# 03_SD_Card.net
KiCad netlist of a schematic drawn in Altium Designer
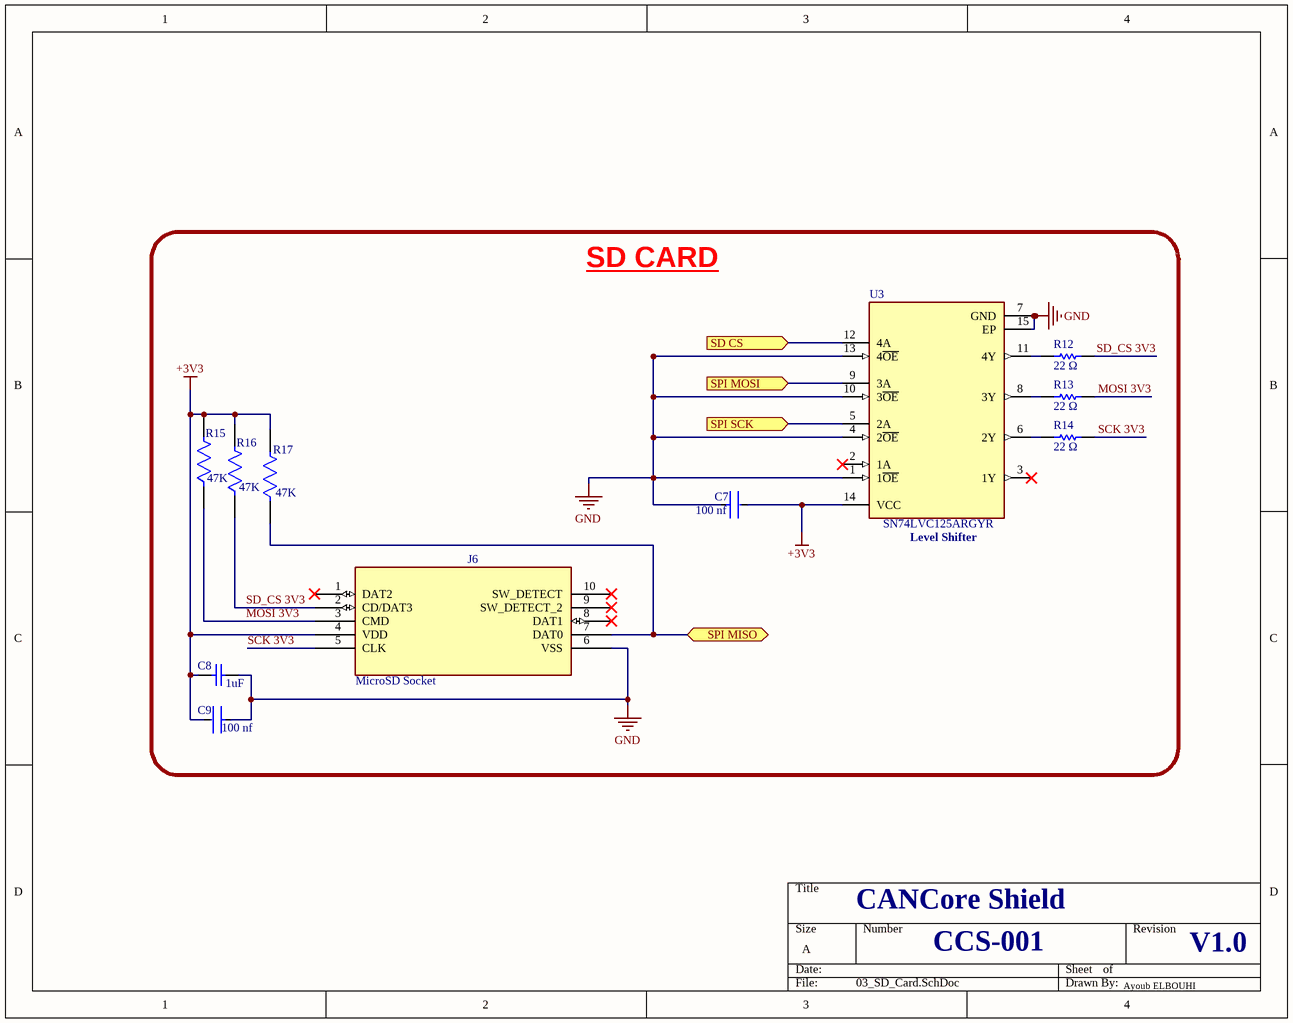
[diagram p0: 03_SD_Card.SchDoc]

(export (version "E")
  (design (tool "Eeschema 10.0.6"))
  (components
    (comp (ref "C7")
      (value "100 nf")
      (footprint "FP-0204-L_0_52_0_05-W_1_0-IPC_B")
      (description "None")
      (fields (field (name "TOLERANCE") "20%"))
      (libsource (lib "Altium Content Vault") (part "b4654b650e69147ec39a6b967a45e02"))
    )
    (comp (ref "C8")
      (value "1uF")
      (footprint "CAPC1608X90X35NL10T15")
      (fields (field (name "PART NUMBER") "GRM188R71A105KA61D") (field (name "MANUFACTURER") "Murata"))
      (libsource (lib "Altium Content Vault") (part "CAP"))
    )
    (comp (ref "C9")
      (value "100 nf")
      (footprint "FP-0204-L_0_52_0_05-W_1_0-IPC_B")
      (description "None")
      (fields (field (name "TOLERANCE") "20%"))
      (libsource (lib "Altium Content Vault") (part "b4654b650e69147ec39a6b967a45e02"))
    )
    (comp (ref "J6")
      (value "MicroSD Socket")
      (footprint "104031-0811_MOL")
      (fields (field (name "MF") "{'manufacturer': u'Molex'}") (field (name "MP") "1040310811"))
      (libsource (lib "1040310811") (part "1040310811"))
    )
    (comp (ref "R12")
      (value "22 Ω")
      (footprint "RESC1608X55X25ML10T15")
      (description "Chip Resistor, 22 Ohm, +/- 1%, 0.1 W, -55 to 155 degC, 0603 (1608 Metric), RoHS, Tape and Reel")
      (libsource (lib "Altium Content Vault") (part "RES-2"))
    )
    (comp (ref "R13")
      (value "22 Ω")
      (footprint "RESC1608X55X25ML10T15")
      (description "Chip Resistor, 22 Ohm, +/- 1%, 0.1 W, -55 to 155 degC, 0603 (1608 Metric), RoHS, Tape and Reel")
      (libsource (lib "Altium Content Vault") (part "RES-2"))
    )
    (comp (ref "R14")
      (value "22 Ω")
      (footprint "RESC1608X55X25ML10T15")
      (description "Chip Resistor, 22 Ohm, +/- 1%, 0.1 W, -55 to 155 degC, 0603 (1608 Metric), RoHS, Tape and Reel")
      (libsource (lib "Altium Content Vault") (part "RES-2"))
    )
    (comp (ref "R15")
      (value "47K")
      (footprint "FP-RC0603FR-0747KL-MFG")
      (description "RES SMD 47K OHM 1% 1/10W 0603")
      (fields (field (name "TOLERANCE") "1%"))
      (libsource (lib "Altium Content Vault") (part "1029c3af85768c4190bb7ad29bc67b5"))
    )
    (comp (ref "R16")
      (value "47K")
      (footprint "FP-RC0603FR-0747KL-MFG")
      (description "RES SMD 47K OHM 1% 1/10W 0603")
      (fields (field (name "TOLERANCE") "1%"))
      (libsource (lib "Altium Content Vault") (part "1029c3af85768c4190bb7ad29bc67b5"))
    )
    (comp (ref "R17")
      (value "47K")
      (footprint "FP-RC0603FR-0747KL-MFG")
      (description "RES SMD 47K OHM 1% 1/10W 0603")
      (fields (field (name "TOLERANCE") "1%"))
      (libsource (lib "Altium Content Vault") (part "1029c3af85768c4190bb7ad29bc67b5"))
    )
    (comp (ref "U3")
      (value "SN74LVC125ARGYR")
      (footprint "FP-RGY0014A-MFG")
      (description "IC BUF NON-INVERT 3.6V 14VQFN")
      (libsource (lib "Altium Content Vault") (part "e6e9db0fccb1960ea3c625b9016e113"))
    )
  )
  (nets
    (net (code "1") (name "+3V3") (class "Default")
      (node (ref "C7") (pin "2") (pinfunction "2_2") (pintype "passive"))
      (node (ref "C8") (pin "2") (pinfunction "2_2") (pintype "passive"))
      (node (ref "C9") (pin "2") (pinfunction "2_2") (pintype "passive"))
      (node (ref "J6") (pin "4") (pinfunction "VDD_4") (pintype "power_in"))
      (node (ref "R15") (pin "2") (pinfunction "2_2") (pintype "passive"))
      (node (ref "R16") (pin "2") (pinfunction "2_2") (pintype "passive"))
      (node (ref "R17") (pin "2") (pinfunction "2_2") (pintype "passive"))
      (node (ref "U3") (pin "14") (pinfunction "VCC_14") (pintype "power_in"))
    )
    (net (code "2") (name "/MOSI 3V3") (class "Default")
      (node (ref "J6") (pin "3") (pinfunction "CMD_3") (pintype "passive"))
      (node (ref "R13") (pin "2") (pinfunction "2_2") (pintype "passive"))
      (node (ref "R15") (pin "1") (pinfunction "1_1") (pintype "passive"))
    )
    (net (code "3") (name "/SCK 3V3") (class "Default")
      (node (ref "J6") (pin "5") (pinfunction "CLK_5") (pintype "passive"))
      (node (ref "R14") (pin "2") (pinfunction "2_2") (pintype "passive"))
    )
    (net (code "4") (name "/SD CS") (class "Default")
      (node (ref "U3") (pin "12") (pinfunction "4A_12") (pintype "passive"))
    )
    (net (code "5") (name "/SD_CS 3V3") (class "Default")
      (node (ref "J6") (pin "2") (pinfunction "CD/DAT3_2") (pintype "bidirectional"))
      (node (ref "R12") (pin "2") (pinfunction "2_2") (pintype "passive"))
      (node (ref "R16") (pin "1") (pinfunction "1_1") (pintype "passive"))
    )
    (net (code "6") (name "/SPI MISO") (class "Default")
      (node (ref "J6") (pin "7") (pinfunction "DAT0_7") (pintype "passive"))
      (node (ref "R17") (pin "1") (pinfunction "1_1") (pintype "passive"))
    )
    (net (code "7") (name "/SPI MOSI") (class "Default")
      (node (ref "U3") (pin "9") (pinfunction "3A_9") (pintype "passive"))
    )
    (net (code "8") (name "/SPI SCK") (class "Default")
      (node (ref "U3") (pin "5") (pinfunction "2A_5") (pintype "passive"))
    )
    (net (code "9") (name "GND") (class "Default")
      (node (ref "C7") (pin "1") (pinfunction "1_1") (pintype "passive"))
      (node (ref "C8") (pin "1") (pinfunction "1_1") (pintype "passive"))
      (node (ref "C9") (pin "1") (pinfunction "1_1") (pintype "passive"))
      (node (ref "J6") (pin "6") (pinfunction "VSS_6") (pintype "passive"))
      (node (ref "U3") (pin "1") (pinfunction "1~{OE}_1") (pintype "input"))
      (node (ref "U3") (pin "10") (pinfunction "3~{OE}_10") (pintype "input"))
      (node (ref "U3") (pin "13") (pinfunction "4~{OE}_13") (pintype "input"))
      (node (ref "U3") (pin "15") (pinfunction "EP_15") (pintype "power_in"))
      (node (ref "U3") (pin "4") (pinfunction "2~{OE}_4") (pintype "input"))
      (node (ref "U3") (pin "7") (pinfunction "GND_7") (pintype "power_in"))
    )
    (net (code "10") (name "Net-(U3-2Y)") (class "Default")
      (node (ref "R14") (pin "1") (pinfunction "1_1") (pintype "passive"))
      (node (ref "U3") (pin "6") (pinfunction "2Y_6") (pintype "output"))
    )
    (net (code "11") (name "Net-(U3-3Y)") (class "Default")
      (node (ref "R13") (pin "1") (pinfunction "1_1") (pintype "passive"))
      (node (ref "U3") (pin "8") (pinfunction "3Y_8") (pintype "output"))
    )
    (net (code "12") (name "Net-(U3-4Y)") (class "Default")
      (node (ref "R12") (pin "1") (pinfunction "1_1") (pintype "passive"))
      (node (ref "U3") (pin "11") (pinfunction "4Y_11") (pintype "output"))
    )
    (net (code "13") (name "unconnected-(J6-DAT1-Pad8)") (class "Default")
      (node (ref "J6") (pin "8") (pinfunction "DAT1_8") (pintype "bidirectional+no_connect"))
    )
    (net (code "14") (name "unconnected-(J6-DAT2-Pad1)") (class "Default")
      (node (ref "J6") (pin "1") (pinfunction "DAT2_1") (pintype "bidirectional+no_connect"))
    )
    (net (code "15") (name "unconnected-(J6-SW_DETECT-Pad10)") (class "Default")
      (node (ref "J6") (pin "10") (pinfunction "SW_DETECT_10") (pintype "passive+no_connect"))
    )
    (net (code "16") (name "unconnected-(J6-SW_DETECT_2-Pad9)") (class "Default")
      (node (ref "J6") (pin "9") (pinfunction "SW_DETECT_2_9") (pintype "passive+no_connect"))
    )
    (net (code "17") (name "unconnected-(U3-1A-Pad2)") (class "Default")
      (node (ref "U3") (pin "2") (pinfunction "1A_2") (pintype "input+no_connect"))
    )
    (net (code "18") (name "unconnected-(U3-1Y-Pad3)") (class "Default")
      (node (ref "U3") (pin "3") (pinfunction "1Y_3") (pintype "output+no_connect"))
    )
  )
)
